# Nintendo64.net
KiCad netlist of a schematic drawn in EAGLE
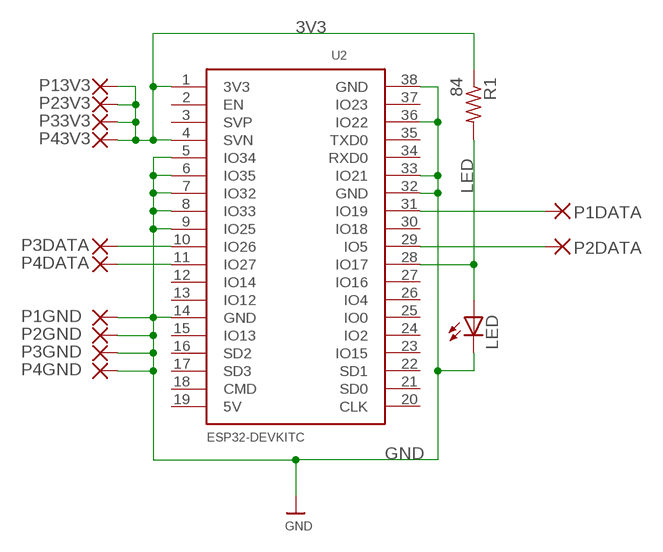
[diagram p0: schematic, sheet 1]

(export (version "E")
  (design (tool "Eeschema 10.0.6"))
  (components
    (comp (ref "LED")
      (value "LEDCHIPLED_1206")
      (footprint "eagle-import:CHIPLED_1206")
      (libsource (lib "eagle-import") (part "LEDCHIPLED_1206"))
    )
    (comp (ref "P1DATA")
      (value "SMD5")
      (footprint "eagle-import:SMD2,54-5,08")
      (libsource (lib "eagle-import") (part "SMD5"))
    )
    (comp (ref "P1GND")
      (value "SMD5")
      (footprint "eagle-import:SMD2,54-5,08")
      (libsource (lib "eagle-import") (part "SMD5"))
    )
    (comp (ref "P2DATA")
      (value "SMD5")
      (footprint "eagle-import:SMD2,54-5,08")
      (libsource (lib "eagle-import") (part "SMD5"))
    )
    (comp (ref "P2GND")
      (value "SMD5")
      (footprint "eagle-import:SMD2,54-5,08")
      (libsource (lib "eagle-import") (part "SMD5"))
    )
    (comp (ref "P3DATA")
      (value "SMD5")
      (footprint "eagle-import:SMD2,54-5,08")
      (libsource (lib "eagle-import") (part "SMD5"))
    )
    (comp (ref "P3GND")
      (value "SMD5")
      (footprint "eagle-import:SMD2,54-5,08")
      (libsource (lib "eagle-import") (part "SMD5"))
    )
    (comp (ref "P4DATA")
      (value "SMD5")
      (footprint "eagle-import:SMD2,54-5,08")
      (libsource (lib "eagle-import") (part "SMD5"))
    )
    (comp (ref "P4GND")
      (value "SMD5")
      (footprint "eagle-import:SMD2,54-5,08")
      (libsource (lib "eagle-import") (part "SMD5"))
    )
    (comp (ref "P13V3")
      (value "SMD5")
      (footprint "eagle-import:SMD2,54-5,08")
      (libsource (lib "eagle-import") (part "SMD5"))
    )
    (comp (ref "P23V3")
      (value "SMD5")
      (footprint "eagle-import:SMD2,54-5,08")
      (libsource (lib "eagle-import") (part "SMD5"))
    )
    (comp (ref "P33V3")
      (value "SMD5")
      (footprint "eagle-import:SMD2,54-5,08")
      (libsource (lib "eagle-import") (part "SMD5"))
    )
    (comp (ref "P43V3")
      (value "SMD5")
      (footprint "eagle-import:SMD2,54-5,08")
      (libsource (lib "eagle-import") (part "SMD5"))
    )
    (comp (ref "R1")
      (value "84")
      (footprint "eagle-import:R1206")
      (libsource (lib "eagle-import") (part "R-US_R1206"))
    )
    (comp (ref "U2")
      (value "ESP32DEVKITC")
      (footprint "eagle-import:ESP32-DEVKITC")
      (libsource (lib "eagle-import") (part "ESP32DEVKITC"))
    )
  )
  (nets
    (net (code "1") (name "/3V3") (class "Default")
      (node (ref "P13V3") (pin "1") (pinfunction "P_1") (pintype "passive"))
      (node (ref "P23V3") (pin "1") (pinfunction "P_1") (pintype "passive"))
      (node (ref "P33V3") (pin "1") (pinfunction "P_1") (pintype "passive"))
      (node (ref "P43V3") (pin "1") (pinfunction "P_1") (pintype "passive"))
      (node (ref "R1") (pin "1") (pinfunction "1_1") (pintype "passive"))
      (node (ref "U2") (pin "1") (pinfunction "3V3_1") (pintype "bidirectional"))
      (node (ref "U2") (pin "4") (pinfunction "SVN_4") (pintype "bidirectional"))
    )
    (net (code "2") (name "/LED") (class "Default")
      (node (ref "LED") (pin "A") (pinfunction "A_A") (pintype "passive"))
      (node (ref "R1") (pin "2") (pinfunction "2_2") (pintype "passive"))
      (node (ref "U2") (pin "28") (pinfunction "IO17_28") (pintype "bidirectional"))
    )
    (net (code "3") (name "GND") (class "Default")
      (node (ref "LED") (pin "C") (pinfunction "C_C") (pintype "passive"))
      (node (ref "P1GND") (pin "1") (pinfunction "P_1") (pintype "passive"))
      (node (ref "P2GND") (pin "1") (pinfunction "P_1") (pintype "passive"))
      (node (ref "P3GND") (pin "1") (pinfunction "P_1") (pintype "passive"))
      (node (ref "P4GND") (pin "1") (pinfunction "P_1") (pintype "passive"))
      (node (ref "U2") (pin "14") (pinfunction "GND_14") (pintype "bidirectional"))
      (node (ref "U2") (pin "32") (pinfunction "GND_32") (pintype "bidirectional"))
      (node (ref "U2") (pin "33") (pinfunction "IO21_33") (pintype "bidirectional"))
      (node (ref "U2") (pin "36") (pinfunction "IO22_36") (pintype "bidirectional"))
      (node (ref "U2") (pin "38") (pinfunction "GND_38") (pintype "bidirectional"))
      (node (ref "U2") (pin "5") (pinfunction "IO34_5") (pintype "bidirectional"))
      (node (ref "U2") (pin "6") (pinfunction "IO35_6") (pintype "bidirectional"))
      (node (ref "U2") (pin "7") (pinfunction "IO32_7") (pintype "bidirectional"))
      (node (ref "U2") (pin "8") (pinfunction "IO33_8") (pintype "bidirectional"))
      (node (ref "U2") (pin "9") (pinfunction "IO25_9") (pintype "bidirectional"))
    )
    (net (code "4") (name "Net-(P1DATA-P)") (class "Default")
      (node (ref "P1DATA") (pin "1") (pinfunction "P_1") (pintype "passive"))
      (node (ref "U2") (pin "31") (pinfunction "IO19_31") (pintype "bidirectional"))
    )
    (net (code "5") (name "Net-(P2DATA-P)") (class "Default")
      (node (ref "P2DATA") (pin "1") (pinfunction "P_1") (pintype "passive"))
      (node (ref "U2") (pin "29") (pinfunction "IO5_29") (pintype "bidirectional"))
    )
    (net (code "6") (name "Net-(P3DATA-P)") (class "Default")
      (node (ref "P3DATA") (pin "1") (pinfunction "P_1") (pintype "passive"))
      (node (ref "U2") (pin "10") (pinfunction "IO26_10") (pintype "bidirectional"))
    )
    (net (code "7") (name "Net-(P4DATA-P)") (class "Default")
      (node (ref "P4DATA") (pin "1") (pinfunction "P_1") (pintype "passive"))
      (node (ref "U2") (pin "11") (pinfunction "IO27_11") (pintype "bidirectional"))
    )
    (net (code "8") (name "unconnected-(U2-5V-Pad19)") (class "Default")
      (node (ref "U2") (pin "19") (pinfunction "5V_19") (pintype "bidirectional"))
    )
    (net (code "9") (name "unconnected-(U2-CLK-Pad20)") (class "Default")
      (node (ref "U2") (pin "20") (pinfunction "CLK_20") (pintype "bidirectional"))
    )
    (net (code "10") (name "unconnected-(U2-CMD-Pad18)") (class "Default")
      (node (ref "U2") (pin "18") (pinfunction "CMD_18") (pintype "bidirectional"))
    )
    (net (code "11") (name "unconnected-(U2-EN-Pad2)") (class "Default")
      (node (ref "U2") (pin "2") (pinfunction "EN_2") (pintype "bidirectional"))
    )
    (net (code "12") (name "unconnected-(U2-IO0-Pad25)") (class "Default")
      (node (ref "U2") (pin "25") (pinfunction "IO0_25") (pintype "bidirectional"))
    )
    (net (code "13") (name "unconnected-(U2-IO2-Pad24)") (class "Default")
      (node (ref "U2") (pin "24") (pinfunction "IO2_24") (pintype "bidirectional"))
    )
    (net (code "14") (name "unconnected-(U2-IO4-Pad26)") (class "Default")
      (node (ref "U2") (pin "26") (pinfunction "IO4_26") (pintype "bidirectional"))
    )
    (net (code "15") (name "unconnected-(U2-IO12-Pad13)") (class "Default")
      (node (ref "U2") (pin "13") (pinfunction "IO12_13") (pintype "bidirectional"))
    )
    (net (code "16") (name "unconnected-(U2-IO13-Pad15)") (class "Default")
      (node (ref "U2") (pin "15") (pinfunction "IO13_15") (pintype "bidirectional"))
    )
    (net (code "17") (name "unconnected-(U2-IO14-Pad12)") (class "Default")
      (node (ref "U2") (pin "12") (pinfunction "IO14_12") (pintype "bidirectional"))
    )
    (net (code "18") (name "unconnected-(U2-IO15-Pad23)") (class "Default")
      (node (ref "U2") (pin "23") (pinfunction "IO15_23") (pintype "bidirectional"))
    )
    (net (code "19") (name "unconnected-(U2-IO16-Pad27)") (class "Default")
      (node (ref "U2") (pin "27") (pinfunction "IO16_27") (pintype "bidirectional"))
    )
    (net (code "20") (name "unconnected-(U2-IO18-Pad30)") (class "Default")
      (node (ref "U2") (pin "30") (pinfunction "IO18_30") (pintype "bidirectional"))
    )
    (net (code "21") (name "unconnected-(U2-IO23-Pad37)") (class "Default")
      (node (ref "U2") (pin "37") (pinfunction "IO23_37") (pintype "bidirectional"))
    )
    (net (code "22") (name "unconnected-(U2-RXD0-Pad34)") (class "Default")
      (node (ref "U2") (pin "34") (pinfunction "RXD0_34") (pintype "bidirectional"))
    )
    (net (code "23") (name "unconnected-(U2-SD0-Pad21)") (class "Default")
      (node (ref "U2") (pin "21") (pinfunction "SD0_21") (pintype "bidirectional"))
    )
    (net (code "24") (name "unconnected-(U2-SD1-Pad22)") (class "Default")
      (node (ref "U2") (pin "22") (pinfunction "SD1_22") (pintype "bidirectional"))
    )
    (net (code "25") (name "unconnected-(U2-SD2-Pad16)") (class "Default")
      (node (ref "U2") (pin "16") (pinfunction "SD2_16") (pintype "bidirectional"))
    )
    (net (code "26") (name "unconnected-(U2-SD3-Pad17)") (class "Default")
      (node (ref "U2") (pin "17") (pinfunction "SD3_17") (pintype "bidirectional"))
    )
    (net (code "27") (name "unconnected-(U2-SVP-Pad3)") (class "Default")
      (node (ref "U2") (pin "3") (pinfunction "SVP_3") (pintype "bidirectional"))
    )
    (net (code "28") (name "unconnected-(U2-TXD0-Pad35)") (class "Default")
      (node (ref "U2") (pin "35") (pinfunction "TXD0_35") (pintype "bidirectional"))
    )
  )
)
